# 1_1_2_Interface_board_Power_Supply.net
KiCad netlist of a schematic drawn in Altium Designer
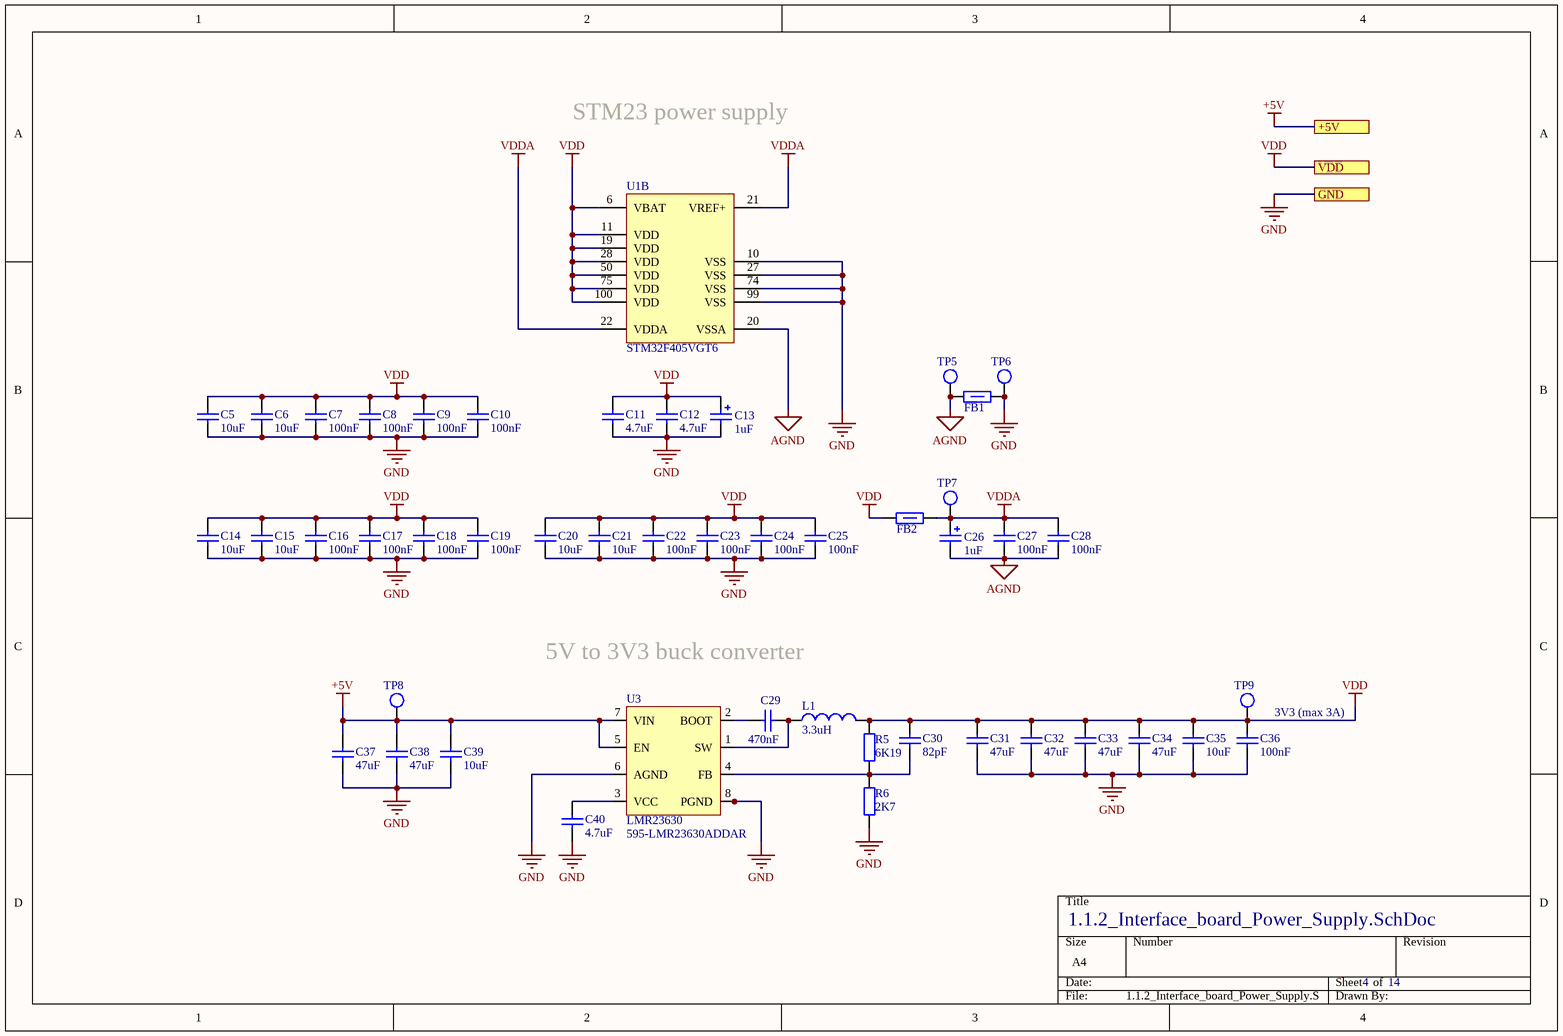
[diagram p0: 1.1.2_Interface_board_Power_Supply.SchDoc]

(export (version "E")
  (design (tool "Eeschema 10.0.6"))
  (components
    (comp (ref "C5")
      (value "10uF")
      (footprint "CAP0805W")
      (description "Capacitor")
      (libsource (lib "Rocket_library") (part "C_10uF_16v"))
    )
    (comp (ref "C6")
      (value "10uF")
      (footprint "CAP0805W")
      (description "Capacitor")
      (libsource (lib "Rocket_library") (part "C_10uF_16v"))
    )
    (comp (ref "C7")
      (value "100nF")
      (footprint "CAP0603R")
      (description "Capacitor")
      (libsource (lib "Rocket_library") (part "C_100nF"))
    )
    (comp (ref "C8")
      (value "100nF")
      (footprint "CAP0603R")
      (description "Capacitor")
      (libsource (lib "Rocket_library") (part "C_100nF"))
    )
    (comp (ref "C9")
      (value "100nF")
      (footprint "CAP0603R")
      (description "Capacitor")
      (libsource (lib "Rocket_library") (part "C_100nF"))
    )
    (comp (ref "C10")
      (value "100nF")
      (footprint "CAP0603R")
      (description "Capacitor")
      (libsource (lib "Rocket_library") (part "C_100nF"))
    )
    (comp (ref "C11")
      (value "4.7uF")
      (footprint "CAP0805W")
      (description "Capacitor")
      (libsource (lib "Rocket_library") (part "C_4.7uF"))
    )
    (comp (ref "C12")
      (value "4.7uF")
      (footprint "CAP0805W")
      (description "Capacitor")
      (libsource (lib "Rocket_library") (part "C_4.7uF"))
    )
    (comp (ref "C13")
      (value "1uF")
      (footprint "CAP1206-case_A")
      (description "Polarized Capacitor")
      (libsource (lib "Rocket_library") (part "C_pol_1uF_tental"))
    )
    (comp (ref "C14")
      (value "10uF")
      (footprint "CAP0805W")
      (description "Capacitor")
      (libsource (lib "Rocket_library") (part "C_10uF_16v"))
    )
    (comp (ref "C15")
      (value "10uF")
      (footprint "CAP0805W")
      (description "Capacitor")
      (libsource (lib "Rocket_library") (part "C_10uF_16v"))
    )
    (comp (ref "C16")
      (value "100nF")
      (footprint "CAP0603R")
      (description "Capacitor")
      (libsource (lib "Rocket_library") (part "C_100nF"))
    )
    (comp (ref "C17")
      (value "100nF")
      (footprint "CAP0603R")
      (description "Capacitor")
      (libsource (lib "Rocket_library") (part "C_100nF"))
    )
    (comp (ref "C18")
      (value "100nF")
      (footprint "CAP0603R")
      (description "Capacitor")
      (libsource (lib "Rocket_library") (part "C_100nF"))
    )
    (comp (ref "C19")
      (value "100nF")
      (footprint "CAP0603R")
      (description "Capacitor")
      (libsource (lib "Rocket_library") (part "C_100nF"))
    )
    (comp (ref "C20")
      (value "10uF")
      (footprint "CAP0805W")
      (description "Capacitor")
      (libsource (lib "Rocket_library") (part "C_10uF_16v"))
    )
    (comp (ref "C21")
      (value "10uF")
      (footprint "CAP0805W")
      (description "Capacitor")
      (libsource (lib "Rocket_library") (part "C_10uF_16v"))
    )
    (comp (ref "C22")
      (value "100nF")
      (footprint "CAP0603R")
      (description "Capacitor")
      (libsource (lib "Rocket_library") (part "C_100nF"))
    )
    (comp (ref "C23")
      (value "100nF")
      (footprint "CAP0603R")
      (description "Capacitor")
      (libsource (lib "Rocket_library") (part "C_100nF"))
    )
    (comp (ref "C24")
      (value "100nF")
      (footprint "CAP0603R")
      (description "Capacitor")
      (libsource (lib "Rocket_library") (part "C_100nF"))
    )
    (comp (ref "C25")
      (value "100nF")
      (footprint "CAP0603R")
      (description "Capacitor")
      (libsource (lib "Rocket_library") (part "C_100nF"))
    )
    (comp (ref "C26")
      (value "1uF")
      (footprint "CAP1206-case_A")
      (description "Polarized Capacitor")
      (libsource (lib "Rocket_library") (part "C_pol_1uF_tental"))
    )
    (comp (ref "C27")
      (value "100nF")
      (footprint "CAP0603R")
      (description "Capacitor")
      (libsource (lib "Rocket_library") (part "C_100nF"))
    )
    (comp (ref "C28")
      (value "100nF")
      (footprint "CAP0603R")
      (description "Capacitor")
      (libsource (lib "Rocket_library") (part "C_100nF"))
    )
    (comp (ref "C29")
      (value "470nF")
      (footprint "CAP0603R")
      (description "Capacitor")
      (libsource (lib "Rocket_library") (part "C_470nF_25v"))
    )
    (comp (ref "C30")
      (value "82pF")
      (footprint "CAP0603R")
      (description "Capacitor")
      (libsource (lib "Rocket_library") (part "C_82pF_50V"))
    )
    (comp (ref "C31")
      (value "47uF")
      (footprint "CAP1206W")
      (description "Capacitor")
      (libsource (lib "Rocket_library") (part "C_47uF_25v_1206"))
    )
    (comp (ref "C32")
      (value "47uF")
      (footprint "CAP1206W")
      (description "Capacitor")
      (libsource (lib "Rocket_library") (part "C_47uF_25v_1206"))
    )
    (comp (ref "C33")
      (value "47uF")
      (footprint "CAP1206W")
      (description "Capacitor")
      (libsource (lib "Rocket_library") (part "C_47uF_25v_1206"))
    )
    (comp (ref "C34")
      (value "47uF")
      (footprint "CAP1206W")
      (description "Capacitor")
      (libsource (lib "Rocket_library") (part "C_47uF_25v_1206"))
    )
    (comp (ref "C35")
      (value "10uF")
      (footprint "CAP0805W")
      (description "Capacitor")
      (libsource (lib "Rocket_library") (part "C_10uF_16v"))
    )
    (comp (ref "C36")
      (value "100nF")
      (footprint "CAP0603R")
      (description "Capacitor")
      (libsource (lib "Rocket_library") (part "C_100nF"))
    )
    (comp (ref "C37")
      (value "47uF")
      (footprint "CAP1206W")
      (description "Capacitor")
      (libsource (lib "Rocket_library") (part "C_47uF_25v_1206"))
    )
    (comp (ref "C38")
      (value "47uF")
      (footprint "CAP1206W")
      (description "Capacitor")
      (libsource (lib "Rocket_library") (part "C_47uF_25v_1206"))
    )
    (comp (ref "C39")
      (value "10uF")
      (footprint "CAP0805W")
      (description "Capacitor")
      (libsource (lib "Rocket_library") (part "C_10uF_16v"))
    )
    (comp (ref "C40")
      (value "4.7uF")
      (footprint "CAP0805W")
      (description "Capacitor")
      (libsource (lib "Rocket_library") (part "C_4.7uF_16v"))
    )
    (comp (ref "FB1")
      (value "81-BLM18KG601SZ1D")
      (footprint "0603")
      (libsource (lib "Rocket_library") (part "Ferrite_bead"))
    )
    (comp (ref "FB2")
      (value "81-BLM18KG601SZ1D")
      (footprint "0603")
      (libsource (lib "Rocket_library") (part "Ferrite_bead"))
    )
    (comp (ref "L1")
      (value "3.3uH")
      (footprint "IHLP-2525CZ-01_Inductor")
      (description "Inductors 3.3uH 20%")
      (libsource (lib "Rocket_library") (part "L_3.3uH_6A"))
    )
    (comp (ref "R5")
      (value "6K19")
      (footprint "0603")
      (description "0.1W 6K19")
      (libsource (lib "Rocket_library") (part "R_0603_01W_6K2"))
    )
    (comp (ref "R6")
      (value "2K7")
      (footprint "0603")
      (description "0.1W 2K7")
      (libsource (lib "Rocket_library") (part "R_0603_01W_2K7"))
    )
    (comp (ref "TP5")
      (value "Test point")
      (footprint "TP")
      (libsource (lib "Rocket_library") (part "Test point"))
    )
    (comp (ref "TP6")
      (value "Test point")
      (footprint "TP")
      (libsource (lib "Rocket_library") (part "Test point"))
    )
    (comp (ref "TP7")
      (value "Test point")
      (footprint "TP")
      (libsource (lib "Rocket_library") (part "Test point"))
    )
    (comp (ref "TP8")
      (value "Test point")
      (footprint "TP")
      (libsource (lib "Rocket_library") (part "Test point"))
    )
    (comp (ref "TP9")
      (value "Test point")
      (footprint "TP")
      (libsource (lib "Rocket_library") (part "Test point"))
    )
    (comp (ref "U1")
      (value "STM32F405VGT6")
      (footprint "STM-LQFP100_N")
      (fields (field (name "MANUFACTURER") "STMicroelectronics"))
      (libsource (lib "STMicroelectronics STM32 F4") (part "STM32F405VGT6"))
    )
    (comp (ref "U3")
      (value "LMR23630")
      (footprint "HSOIC-8")
      (description "Voltage regulator 3A")
      (fields (field (name "SUPPLIER PART NUMBER 1") "595-LMR23630ADDAR"))
      (libsource (lib "Rocket_library") (part "LMR23630"))
    )
  )
  (nets
    (net (code "1") (name "+5V") (class "Default")
      (node (ref "C37") (pin "2") (pinfunction "2_2") (pintype "passive"))
      (node (ref "C38") (pin "2") (pinfunction "2_2") (pintype "passive"))
      (node (ref "C39") (pin "2") (pinfunction "2_2") (pintype "passive"))
      (node (ref "TP8") (pin "1") (pinfunction "1_1") (pintype "passive"))
      (node (ref "U3") (pin "5") (pinfunction "EN_5") (pintype "passive"))
      (node (ref "U3") (pin "7") (pinfunction "VIN_7") (pintype "passive"))
    )
    (net (code "2") (name "AGND") (class "Default")
      (node (ref "C26") (pin "2") (pinfunction "2_2") (pintype "passive"))
      (node (ref "C27") (pin "1") (pinfunction "1_1") (pintype "passive"))
      (node (ref "C28") (pin "1") (pinfunction "1_1") (pintype "passive"))
      (node (ref "FB1") (pin "1") (pinfunction "1_1") (pintype "passive"))
      (node (ref "TP5") (pin "1") (pinfunction "1_1") (pintype "passive"))
      (node (ref "U1") (pin "20") (pinfunction "VSSA_20") (pintype "power_in"))
    )
    (net (code "3") (name "GND") (class "Default")
      (node (ref "C10") (pin "1") (pinfunction "1_1") (pintype "passive"))
      (node (ref "C11") (pin "1") (pinfunction "1_1") (pintype "passive"))
      (node (ref "C12") (pin "1") (pinfunction "1_1") (pintype "passive"))
      (node (ref "C13") (pin "2") (pinfunction "2_2") (pintype "passive"))
      (node (ref "C14") (pin "1") (pinfunction "1_1") (pintype "passive"))
      (node (ref "C15") (pin "1") (pinfunction "1_1") (pintype "passive"))
      (node (ref "C16") (pin "1") (pinfunction "1_1") (pintype "passive"))
      (node (ref "C17") (pin "1") (pinfunction "1_1") (pintype "passive"))
      (node (ref "C18") (pin "1") (pinfunction "1_1") (pintype "passive"))
      (node (ref "C19") (pin "1") (pinfunction "1_1") (pintype "passive"))
      (node (ref "C20") (pin "1") (pinfunction "1_1") (pintype "passive"))
      (node (ref "C21") (pin "1") (pinfunction "1_1") (pintype "passive"))
      (node (ref "C22") (pin "1") (pinfunction "1_1") (pintype "passive"))
      (node (ref "C23") (pin "1") (pinfunction "1_1") (pintype "passive"))
      (node (ref "C24") (pin "1") (pinfunction "1_1") (pintype "passive"))
      (node (ref "C25") (pin "1") (pinfunction "1_1") (pintype "passive"))
      (node (ref "C31") (pin "1") (pinfunction "1_1") (pintype "passive"))
      (node (ref "C32") (pin "1") (pinfunction "1_1") (pintype "passive"))
      (node (ref "C33") (pin "1") (pinfunction "1_1") (pintype "passive"))
      (node (ref "C34") (pin "1") (pinfunction "1_1") (pintype "passive"))
      (node (ref "C35") (pin "1") (pinfunction "1_1") (pintype "passive"))
      (node (ref "C36") (pin "1") (pinfunction "1_1") (pintype "passive"))
      (node (ref "C37") (pin "1") (pinfunction "1_1") (pintype "passive"))
      (node (ref "C38") (pin "1") (pinfunction "1_1") (pintype "passive"))
      (node (ref "C39") (pin "1") (pinfunction "1_1") (pintype "passive"))
      (node (ref "C40") (pin "1") (pinfunction "1_1") (pintype "passive"))
      (node (ref "C5") (pin "1") (pinfunction "1_1") (pintype "passive"))
      (node (ref "C6") (pin "1") (pinfunction "1_1") (pintype "passive"))
      (node (ref "C7") (pin "1") (pinfunction "1_1") (pintype "passive"))
      (node (ref "C8") (pin "1") (pinfunction "1_1") (pintype "passive"))
      (node (ref "C9") (pin "1") (pinfunction "1_1") (pintype "passive"))
      (node (ref "FB1") (pin "2") (pinfunction "2_2") (pintype "passive"))
      (node (ref "R6") (pin "1") (pinfunction "1_1") (pintype "passive"))
      (node (ref "TP6") (pin "1") (pinfunction "1_1") (pintype "passive"))
      (node (ref "U1") (pin "10") (pinfunction "VSS_10") (pintype "power_in"))
      (node (ref "U1") (pin "27") (pinfunction "VSS_27") (pintype "power_in"))
      (node (ref "U1") (pin "74") (pinfunction "VSS_74") (pintype "power_in"))
      (node (ref "U1") (pin "99") (pinfunction "VSS_99") (pintype "power_in"))
      (node (ref "U3") (pin "6") (pinfunction "AGND_6") (pintype "passive"))
      (node (ref "U3") (pin "8") (pinfunction "PGND_8") (pintype "passive"))
      (node (ref "U3") (pin "PD") (pinfunction "PGND_PD") (pintype "passive"))
    )
    (net (code "4") (name "Net-(U3-BOOT)") (class "Default")
      (node (ref "C29") (pin "2") (pinfunction "2_2") (pintype "passive"))
      (node (ref "U3") (pin "2") (pinfunction "BOOT_2") (pintype "passive"))
    )
    (net (code "5") (name "Net-(U3-FB)") (class "Default")
      (node (ref "C30") (pin "1") (pinfunction "1_1") (pintype "passive"))
      (node (ref "R5") (pin "1") (pinfunction "1_1") (pintype "passive"))
      (node (ref "R6") (pin "2") (pinfunction "2_2") (pintype "passive"))
      (node (ref "U3") (pin "4") (pinfunction "FB_4") (pintype "passive"))
    )
    (net (code "6") (name "Net-(U3-SW)") (class "Default")
      (node (ref "C29") (pin "1") (pinfunction "1_1") (pintype "passive"))
      (node (ref "L1") (pin "1") (pinfunction "1_1") (pintype "passive"))
      (node (ref "U3") (pin "1") (pinfunction "SW_1") (pintype "passive"))
    )
    (net (code "7") (name "Net-(U3-VCC)") (class "Default")
      (node (ref "C40") (pin "2") (pinfunction "2_2") (pintype "passive"))
      (node (ref "U3") (pin "3") (pinfunction "VCC_3") (pintype "passive"))
    )
    (net (code "8") (name "VDD") (class "Default")
      (node (ref "C10") (pin "2") (pinfunction "2_2") (pintype "passive"))
      (node (ref "C11") (pin "2") (pinfunction "2_2") (pintype "passive"))
      (node (ref "C12") (pin "2") (pinfunction "2_2") (pintype "passive"))
      (node (ref "C13") (pin "1") (pinfunction "1_1") (pintype "passive"))
      (node (ref "C14") (pin "2") (pinfunction "2_2") (pintype "passive"))
      (node (ref "C15") (pin "2") (pinfunction "2_2") (pintype "passive"))
      (node (ref "C16") (pin "2") (pinfunction "2_2") (pintype "passive"))
      (node (ref "C17") (pin "2") (pinfunction "2_2") (pintype "passive"))
      (node (ref "C18") (pin "2") (pinfunction "2_2") (pintype "passive"))
      (node (ref "C19") (pin "2") (pinfunction "2_2") (pintype "passive"))
      (node (ref "C20") (pin "2") (pinfunction "2_2") (pintype "passive"))
      (node (ref "C21") (pin "2") (pinfunction "2_2") (pintype "passive"))
      (node (ref "C22") (pin "2") (pinfunction "2_2") (pintype "passive"))
      (node (ref "C23") (pin "2") (pinfunction "2_2") (pintype "passive"))
      (node (ref "C24") (pin "2") (pinfunction "2_2") (pintype "passive"))
      (node (ref "C25") (pin "2") (pinfunction "2_2") (pintype "passive"))
      (node (ref "C30") (pin "2") (pinfunction "2_2") (pintype "passive"))
      (node (ref "C31") (pin "2") (pinfunction "2_2") (pintype "passive"))
      (node (ref "C32") (pin "2") (pinfunction "2_2") (pintype "passive"))
      (node (ref "C33") (pin "2") (pinfunction "2_2") (pintype "passive"))
      (node (ref "C34") (pin "2") (pinfunction "2_2") (pintype "passive"))
      (node (ref "C35") (pin "2") (pinfunction "2_2") (pintype "passive"))
      (node (ref "C36") (pin "2") (pinfunction "2_2") (pintype "passive"))
      (node (ref "C5") (pin "2") (pinfunction "2_2") (pintype "passive"))
      (node (ref "C6") (pin "2") (pinfunction "2_2") (pintype "passive"))
      (node (ref "C7") (pin "2") (pinfunction "2_2") (pintype "passive"))
      (node (ref "C8") (pin "2") (pinfunction "2_2") (pintype "passive"))
      (node (ref "C9") (pin "2") (pinfunction "2_2") (pintype "passive"))
      (node (ref "FB2") (pin "1") (pinfunction "1_1") (pintype "passive"))
      (node (ref "L1") (pin "2") (pinfunction "2_2") (pintype "passive"))
      (node (ref "R5") (pin "2") (pinfunction "2_2") (pintype "passive"))
      (node (ref "TP9") (pin "1") (pinfunction "1_1") (pintype "passive"))
      (node (ref "U1") (pin "100") (pinfunction "VDD_100") (pintype "power_in"))
      (node (ref "U1") (pin "11") (pinfunction "VDD_11") (pintype "power_in"))
      (node (ref "U1") (pin "19") (pinfunction "VDD_19") (pintype "power_in"))
      (node (ref "U1") (pin "28") (pinfunction "VDD_28") (pintype "power_in"))
      (node (ref "U1") (pin "50") (pinfunction "VDD_50") (pintype "power_in"))
      (node (ref "U1") (pin "6") (pinfunction "VBAT_6") (pintype "power_in"))
      (node (ref "U1") (pin "75") (pinfunction "VDD_75") (pintype "power_in"))
    )
    (net (code "9") (name "VDDA") (class "Default")
      (node (ref "C26") (pin "1") (pinfunction "1_1") (pintype "passive"))
      (node (ref "C27") (pin "2") (pinfunction "2_2") (pintype "passive"))
      (node (ref "C28") (pin "2") (pinfunction "2_2") (pintype "passive"))
      (node (ref "FB2") (pin "2") (pinfunction "2_2") (pintype "passive"))
      (node (ref "TP7") (pin "1") (pinfunction "1_1") (pintype "passive"))
      (node (ref "U1") (pin "21") (pinfunction "VREF+_21") (pintype "power_in"))
      (node (ref "U1") (pin "22") (pinfunction "VDDA_22") (pintype "power_in"))
    )
  )
)
